# Actuator_Circle.net
KiCad netlist of a schematic drawn in EAGLE
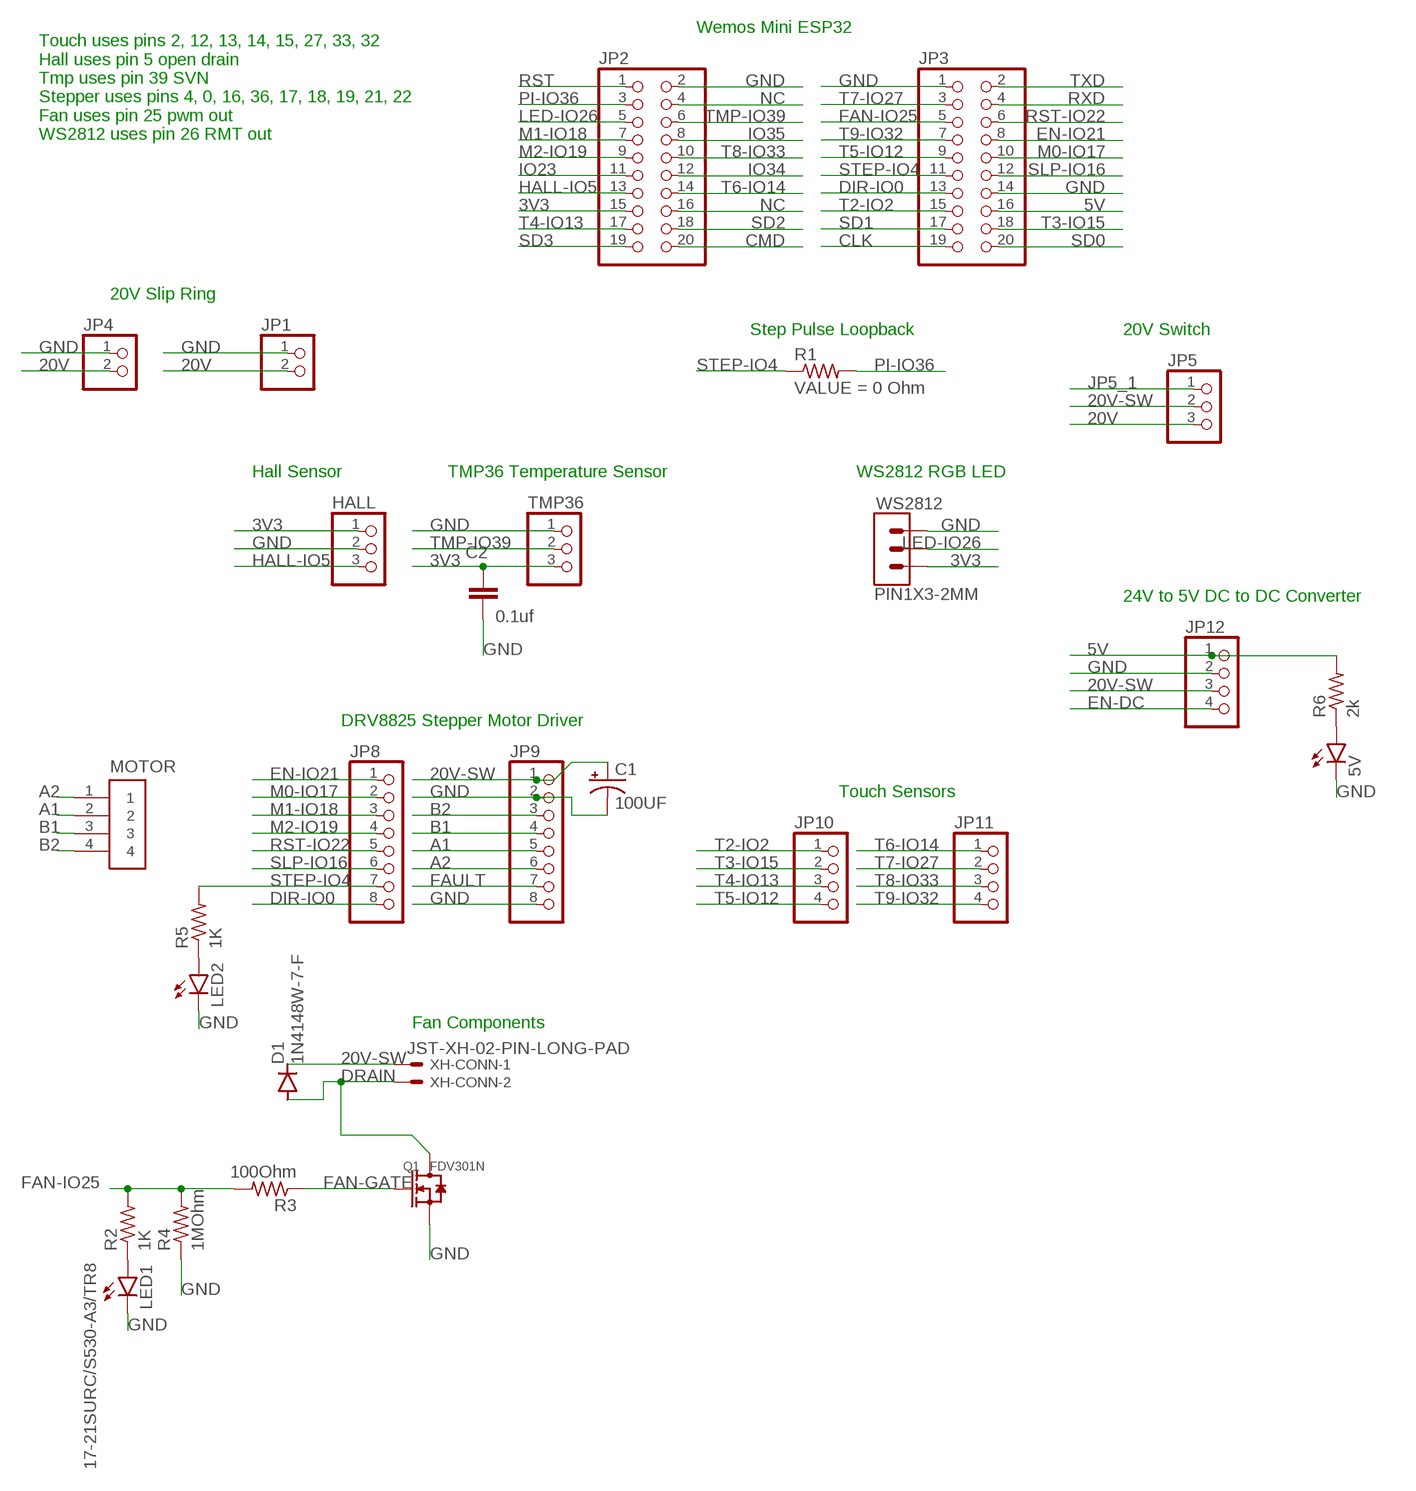
[diagram p0: schematic, sheet 1]

(export (version "E")
  (design (tool "Eeschema 10.0.6"))
  (components
    (comp (ref "5V")
      (value "17-21SURC/S530-A3/TR8")
      (footprint "eagle-import:CHIPLED_0805")
      (libsource (lib "eagle-import") (part "LEDCHIPLED_0805"))
    )
    (comp (ref "C1")
      (value "100UF")
      (footprint "eagle-import:E2,5-6")
      (libsource (lib "eagle-import") (part "CAPACITOR-PE2.5-6"))
    )
    (comp (ref "C2")
      (value "0.1uf")
      (footprint "eagle-import:CAP_0603")
      (fields
        (field (name "DIGIKEY_PART_NUMBER") "LCSC Part #: C86295")
        (field (name "MANUFACTURER") "Samsung Electro-Mechanics")
        (field (name "MPN") " CL10A226MP8NUNE")
        (field (name "CREATED_BY") "ChiliPeppr")
      )
      (libsource (lib "eagle-import") (part "CAP-0603-22UF-10V-MLCC"))
    )
    (comp (ref "D1")
      (value "1N4148W-7-F")
      (footprint "eagle-import:SOD123")
      (libsource (lib "eagle-import") (part "D-SOD123"))
    )
    (comp (ref "HALL")
      (value "PINHD-1X3")
      (footprint "eagle-import:1X03")
      (libsource (lib "eagle-import") (part "pinhead_325_PINHD-1X3"))
    )
    (comp (ref "JP1")
      (value "PINHD-1X2")
      (footprint "eagle-import:1X02")
      (libsource (lib "eagle-import") (part "PINHD-1X2"))
    )
    (comp (ref "JP2")
      (value "PINHD-2X10")
      (footprint "eagle-import:2X10")
      (libsource (lib "eagle-import") (part "PINHD-2X10"))
    )
    (comp (ref "JP3")
      (value "PINHD-2X10")
      (footprint "eagle-import:2X10")
      (libsource (lib "eagle-import") (part "PINHD-2X10"))
    )
    (comp (ref "JP4")
      (value "PINHD-1X2")
      (footprint "eagle-import:1X02")
      (libsource (lib "eagle-import") (part "PINHD-1X2"))
    )
    (comp (ref "JP5")
      (value "PINHD-1X3/90")
      (footprint "eagle-import:1X03_90")
      (libsource (lib "eagle-import") (part "PINHD-1X3/90"))
    )
    (comp (ref "JP8")
      (value "PINHD-1X8")
      (footprint "eagle-import:1X08")
      (libsource (lib "eagle-import") (part "PINHD-1X8"))
    )
    (comp (ref "JP9")
      (value "PINHD-1X8")
      (footprint "eagle-import:1X08")
      (libsource (lib "eagle-import") (part "PINHD-1X8"))
    )
    (comp (ref "JP10")
      (value "PINHD-1X4")
      (footprint "eagle-import:1X04")
      (libsource (lib "eagle-import") (part "PINHD-1X4"))
    )
    (comp (ref "JP11")
      (value "PINHD-1X4")
      (footprint "eagle-import:1X04")
      (libsource (lib "eagle-import") (part "PINHD-1X4"))
    )
    (comp (ref "JP12")
      (value "PINHD-1X4")
      (footprint "eagle-import:1X04")
      (libsource (lib "eagle-import") (part "PINHD-1X4"))
    )
    (comp (ref "LED1")
      (value "17-21SURC/S530-A3/TR8")
      (footprint "eagle-import:CHIPLED_0805")
      (libsource (lib "eagle-import") (part "LEDCHIPLED_0805"))
    )
    (comp (ref "LED2")
      (value "17-21SURC/S530-A3/TR8")
      (footprint "eagle-import:CHIPLED_0805")
      (libsource (lib "eagle-import") (part "LEDCHIPLED_0805"))
    )
    (comp (ref "MOTOR")
      (value "B4B-PH-K-S(LF)(SN)")
      (footprint "eagle-import:JST_B4B-PH-K-S(LF)(SN)")
      (fields (field (name "MF") "JST Sales") (field (name "MP") "B4B-PH-K-S_LF__SN_"))
      (libsource (lib "eagle-import") (part "B4B-PH-K-S(LF)(SN)"))
    )
    (comp (ref "Q1")
      (value "FDV301N")
      (footprint "eagle-import:SOT23")
      (libsource (lib "eagle-import") (part "SMD-MOSFET-N-CH-25V-220MA-FDV301N(SOT-23)"))
    )
    (comp (ref "R1")
      (value "0 Ohm")
      (footprint "eagle-import:RES_0402")
      (fields (field (name "CREATED_BY") "ChiliPeppr"))
      (libsource (lib "eagle-import") (part "robot actuator_11740443_RES-0402"))
    )
    (comp (ref "R2")
      (value "1K")
      (footprint "eagle-import:RES_0402")
      (fields (field (name "CREATED_BY") "ChiliPeppr"))
      (libsource (lib "eagle-import") (part "RES-0402"))
    )
    (comp (ref "R3")
      (value "100Ohm")
      (footprint "eagle-import:RES_0402")
      (fields (field (name "CREATED_BY") "ChiliPeppr"))
      (libsource (lib "eagle-import") (part "RES-0402"))
    )
    (comp (ref "R4")
      (value "1MOhm")
      (footprint "eagle-import:RES_0402")
      (fields (field (name "CREATED_BY") "ChiliPeppr"))
      (libsource (lib "eagle-import") (part "RES-0402"))
    )
    (comp (ref "R5")
      (value "1K")
      (footprint "eagle-import:RES_0402")
      (fields (field (name "CREATED_BY") "ChiliPeppr"))
      (libsource (lib "eagle-import") (part "RES-0402"))
    )
    (comp (ref "R6")
      (value "2k")
      (footprint "eagle-import:RES_0402")
      (fields (field (name "CREATED_BY") "ChiliPeppr"))
      (libsource (lib "eagle-import") (part "RES-0402"))
    )
    (comp (ref "TMP36")
      (value "PINHD-1X3")
      (footprint "eagle-import:1X03")
      (libsource (lib "eagle-import") (part "pinhead_325_PINHD-1X3"))
    )
    (comp (ref "WS2812")
      (value "PIN1X3-2MM")
      (footprint "eagle-import:PIN1X3-2MM")
      (fields
        (field (name "MANUFACTURER") " Würth Elektronik ")
        (field (name "MPN") "62000311121")
        (field (name "CREATED_BY") "PCBLayout.com")
      )
      (libsource (lib "eagle-import") (part "PIN1X3-2MM"))
    )
    (comp (ref "XH-CONN")
      (value "JST-XH-02-PIN-LONG-PAD")
      (footprint "eagle-import:JST-XH-02-PACKAGE-LONG-PAD")
      (libsource (lib "eagle-import") (part "JST-XH-02-PIN-LONG-PAD"))
    )
  )
  (nets
    (net (code "1") (name "/3V3") (class "Default")
      (node (ref "C2") (pin "1") (pinfunction "1_1") (pintype "passive"))
      (node (ref "HALL") (pin "1") (pinfunction "1_1") (pintype "passive"))
      (node (ref "JP2") (pin "15") (pinfunction "15_15") (pintype "passive"))
      (node (ref "TMP36") (pin "3") (pinfunction "3_3") (pintype "passive"))
      (node (ref "WS2812") (pin "3") (pinfunction "3_3") (pintype "passive"))
    )
    (net (code "2") (name "/5V") (class "Default")
      (node (ref "JP12") (pin "1") (pinfunction "1_1") (pintype "passive"))
      (node (ref "JP3") (pin "16") (pinfunction "16_16") (pintype "passive"))
      (node (ref "R6") (pin "2") (pinfunction "2_2") (pintype "passive"))
    )
    (net (code "3") (name "/20V") (class "Default")
      (node (ref "JP1") (pin "2") (pinfunction "2_2") (pintype "passive"))
      (node (ref "JP4") (pin "2") (pinfunction "2_2") (pintype "passive"))
      (node (ref "JP5") (pin "3") (pinfunction "3_3") (pintype "passive"))
    )
    (net (code "4") (name "/20V-SW") (class "Default")
      (node (ref "C1") (pin "+") (pinfunction "+_+") (pintype "passive"))
      (node (ref "D1") (pin "1") (pinfunction "C_1") (pintype "passive"))
      (node (ref "JP12") (pin "3") (pinfunction "3_3") (pintype "passive"))
      (node (ref "JP5") (pin "2") (pinfunction "2_2") (pintype "passive"))
      (node (ref "JP9") (pin "1") (pinfunction "1_1") (pintype "passive"))
      (node (ref "XH-CONN") (pin "1") (pinfunction "S_1") (pintype "passive"))
    )
    (net (code "5") (name "/A1") (class "Default")
      (node (ref "JP9") (pin "5") (pinfunction "5_5") (pintype "passive"))
      (node (ref "MOTOR") (pin "2") (pinfunction "2_2") (pintype "passive"))
    )
    (net (code "6") (name "/A2") (class "Default")
      (node (ref "JP9") (pin "6") (pinfunction "6_6") (pintype "passive"))
      (node (ref "MOTOR") (pin "1") (pinfunction "1_1") (pintype "passive"))
    )
    (net (code "7") (name "/B1") (class "Default")
      (node (ref "JP9") (pin "4") (pinfunction "4_4") (pintype "passive"))
      (node (ref "MOTOR") (pin "3") (pinfunction "3_3") (pintype "passive"))
    )
    (net (code "8") (name "/B2") (class "Default")
      (node (ref "JP9") (pin "3") (pinfunction "3_3") (pintype "passive"))
      (node (ref "MOTOR") (pin "4") (pinfunction "4_4") (pintype "passive"))
    )
    (net (code "9") (name "/CLK") (class "Default")
      (node (ref "JP3") (pin "19") (pinfunction "19_19") (pintype "passive"))
    )
    (net (code "10") (name "/CMD") (class "Default")
      (node (ref "JP2") (pin "20") (pinfunction "20_20") (pintype "passive"))
    )
    (net (code "11") (name "/DIR-IO0") (class "Default")
      (node (ref "JP3") (pin "13") (pinfunction "13_13") (pintype "passive"))
      (node (ref "JP8") (pin "8") (pinfunction "8_8") (pintype "passive"))
    )
    (net (code "12") (name "/DRAIN") (class "Default")
      (node (ref "D1") (pin "2") (pinfunction "A_2") (pintype "passive"))
      (node (ref "Q1") (pin "3") (pinfunction "D_3") (pintype "passive"))
      (node (ref "XH-CONN") (pin "2") (pinfunction "S_2") (pintype "passive"))
    )
    (net (code "13") (name "/EN-DC") (class "Default")
      (node (ref "JP12") (pin "4") (pinfunction "4_4") (pintype "passive"))
    )
    (net (code "14") (name "/EN-IO21") (class "Default")
      (node (ref "JP3") (pin "8") (pinfunction "8_8") (pintype "passive"))
      (node (ref "JP8") (pin "1") (pinfunction "1_1") (pintype "passive"))
    )
    (net (code "15") (name "/FAN-GATE") (class "Default")
      (node (ref "Q1") (pin "1") (pinfunction "G_1") (pintype "passive"))
      (node (ref "R3") (pin "1") (pinfunction "1_1") (pintype "passive"))
    )
    (net (code "16") (name "/FAN-IO25") (class "Default")
      (node (ref "JP3") (pin "5") (pinfunction "5_5") (pintype "passive"))
      (node (ref "R2") (pin "2") (pinfunction "2_2") (pintype "passive"))
      (node (ref "R3") (pin "2") (pinfunction "2_2") (pintype "passive"))
      (node (ref "R4") (pin "2") (pinfunction "2_2") (pintype "passive"))
    )
    (net (code "17") (name "/FAULT") (class "Default")
      (node (ref "JP9") (pin "7") (pinfunction "7_7") (pintype "passive"))
    )
    (net (code "18") (name "/GND") (class "Default")
      (node (ref "5V") (pin "C") (pinfunction "C_C") (pintype "passive"))
      (node (ref "C1") (pin "-") (pinfunction "-_-") (pintype "passive"))
      (node (ref "C2") (pin "2") (pinfunction "2_2") (pintype "passive"))
      (node (ref "HALL") (pin "2") (pinfunction "2_2") (pintype "passive"))
      (node (ref "JP1") (pin "1") (pinfunction "1_1") (pintype "passive"))
      (node (ref "JP12") (pin "2") (pinfunction "2_2") (pintype "passive"))
      (node (ref "JP2") (pin "2") (pinfunction "2_2") (pintype "passive"))
      (node (ref "JP3") (pin "1") (pinfunction "1_1") (pintype "passive"))
      (node (ref "JP3") (pin "14") (pinfunction "14_14") (pintype "passive"))
      (node (ref "JP4") (pin "1") (pinfunction "1_1") (pintype "passive"))
      (node (ref "JP9") (pin "2") (pinfunction "2_2") (pintype "passive"))
      (node (ref "JP9") (pin "8") (pinfunction "8_8") (pintype "passive"))
      (node (ref "LED1") (pin "C") (pinfunction "C_C") (pintype "passive"))
      (node (ref "LED2") (pin "C") (pinfunction "C_C") (pintype "passive"))
      (node (ref "Q1") (pin "2") (pinfunction "S_2") (pintype "passive"))
      (node (ref "R4") (pin "1") (pinfunction "1_1") (pintype "passive"))
      (node (ref "TMP36") (pin "1") (pinfunction "1_1") (pintype "passive"))
      (node (ref "WS2812") (pin "1") (pinfunction "1_1") (pintype "passive"))
    )
    (net (code "19") (name "/HALL-IO5") (class "Default")
      (node (ref "HALL") (pin "3") (pinfunction "3_3") (pintype "passive"))
      (node (ref "JP2") (pin "13") (pinfunction "13_13") (pintype "passive"))
    )
    (net (code "20") (name "/IO23") (class "Default")
      (node (ref "JP2") (pin "11") (pinfunction "11_11") (pintype "passive"))
    )
    (net (code "21") (name "/IO34") (class "Default")
      (node (ref "JP2") (pin "12") (pinfunction "12_12") (pintype "passive"))
    )
    (net (code "22") (name "/IO35") (class "Default")
      (node (ref "JP2") (pin "8") (pinfunction "8_8") (pintype "passive"))
    )
    (net (code "23") (name "/JP5_1") (class "Default")
      (node (ref "JP5") (pin "1") (pinfunction "1_1") (pintype "passive"))
    )
    (net (code "24") (name "/LED-IO26") (class "Default")
      (node (ref "JP2") (pin "5") (pinfunction "5_5") (pintype "passive"))
      (node (ref "WS2812") (pin "2") (pinfunction "2_2") (pintype "passive"))
    )
    (net (code "25") (name "/M0-IO17") (class "Default")
      (node (ref "JP3") (pin "10") (pinfunction "10_10") (pintype "passive"))
      (node (ref "JP8") (pin "2") (pinfunction "2_2") (pintype "passive"))
    )
    (net (code "26") (name "/M1-IO18") (class "Default")
      (node (ref "JP2") (pin "7") (pinfunction "7_7") (pintype "passive"))
      (node (ref "JP8") (pin "3") (pinfunction "3_3") (pintype "passive"))
    )
    (net (code "27") (name "/M2-IO19") (class "Default")
      (node (ref "JP2") (pin "9") (pinfunction "9_9") (pintype "passive"))
      (node (ref "JP8") (pin "4") (pinfunction "4_4") (pintype "passive"))
    )
    (net (code "28") (name "/NC") (class "Default")
      (node (ref "JP2") (pin "16") (pinfunction "16_16") (pintype "passive"))
      (node (ref "JP2") (pin "4") (pinfunction "4_4") (pintype "passive"))
    )
    (net (code "29") (name "/PI-IO36") (class "Default")
      (node (ref "JP2") (pin "3") (pinfunction "3_3") (pintype "passive"))
      (node (ref "R1") (pin "2") (pinfunction "2_2") (pintype "passive"))
    )
    (net (code "30") (name "/RST") (class "Default")
      (node (ref "JP2") (pin "1") (pinfunction "1_1") (pintype "passive"))
    )
    (net (code "31") (name "/RST-IO22") (class "Default")
      (node (ref "JP3") (pin "6") (pinfunction "6_6") (pintype "passive"))
      (node (ref "JP8") (pin "5") (pinfunction "5_5") (pintype "passive"))
    )
    (net (code "32") (name "/RXD") (class "Default")
      (node (ref "JP3") (pin "4") (pinfunction "4_4") (pintype "passive"))
    )
    (net (code "33") (name "/SD0") (class "Default")
      (node (ref "JP3") (pin "20") (pinfunction "20_20") (pintype "passive"))
    )
    (net (code "34") (name "/SD1") (class "Default")
      (node (ref "JP3") (pin "17") (pinfunction "17_17") (pintype "passive"))
    )
    (net (code "35") (name "/SD2") (class "Default")
      (node (ref "JP2") (pin "18") (pinfunction "18_18") (pintype "passive"))
    )
    (net (code "36") (name "/SD3") (class "Default")
      (node (ref "JP2") (pin "19") (pinfunction "19_19") (pintype "passive"))
    )
    (net (code "37") (name "/SLP-IO16") (class "Default")
      (node (ref "JP3") (pin "12") (pinfunction "12_12") (pintype "passive"))
      (node (ref "JP8") (pin "6") (pinfunction "6_6") (pintype "passive"))
    )
    (net (code "38") (name "/STEP-IO4") (class "Default")
      (node (ref "JP3") (pin "11") (pinfunction "11_11") (pintype "passive"))
      (node (ref "JP8") (pin "7") (pinfunction "7_7") (pintype "passive"))
      (node (ref "R1") (pin "1") (pinfunction "1_1") (pintype "passive"))
      (node (ref "R5") (pin "2") (pinfunction "2_2") (pintype "passive"))
    )
    (net (code "39") (name "/T2-IO2") (class "Default")
      (node (ref "JP10") (pin "1") (pinfunction "1_1") (pintype "passive"))
      (node (ref "JP3") (pin "15") (pinfunction "15_15") (pintype "passive"))
    )
    (net (code "40") (name "/T3-IO15") (class "Default")
      (node (ref "JP10") (pin "2") (pinfunction "2_2") (pintype "passive"))
      (node (ref "JP3") (pin "18") (pinfunction "18_18") (pintype "passive"))
    )
    (net (code "41") (name "/T4-IO13") (class "Default")
      (node (ref "JP10") (pin "3") (pinfunction "3_3") (pintype "passive"))
      (node (ref "JP2") (pin "17") (pinfunction "17_17") (pintype "passive"))
    )
    (net (code "42") (name "/T5-IO12") (class "Default")
      (node (ref "JP10") (pin "4") (pinfunction "4_4") (pintype "passive"))
      (node (ref "JP3") (pin "9") (pinfunction "9_9") (pintype "passive"))
    )
    (net (code "43") (name "/T6-IO14") (class "Default")
      (node (ref "JP11") (pin "1") (pinfunction "1_1") (pintype "passive"))
      (node (ref "JP2") (pin "14") (pinfunction "14_14") (pintype "passive"))
    )
    (net (code "44") (name "/T7-IO27") (class "Default")
      (node (ref "JP11") (pin "2") (pinfunction "2_2") (pintype "passive"))
      (node (ref "JP3") (pin "3") (pinfunction "3_3") (pintype "passive"))
    )
    (net (code "45") (name "/T8-IO33") (class "Default")
      (node (ref "JP11") (pin "3") (pinfunction "3_3") (pintype "passive"))
      (node (ref "JP2") (pin "10") (pinfunction "10_10") (pintype "passive"))
    )
    (net (code "46") (name "/T9-IO32") (class "Default")
      (node (ref "JP11") (pin "4") (pinfunction "4_4") (pintype "passive"))
      (node (ref "JP3") (pin "7") (pinfunction "7_7") (pintype "passive"))
    )
    (net (code "47") (name "/TMP-IO39") (class "Default")
      (node (ref "JP2") (pin "6") (pinfunction "6_6") (pintype "passive"))
      (node (ref "TMP36") (pin "2") (pinfunction "2_2") (pintype "passive"))
    )
    (net (code "48") (name "/TXD") (class "Default")
      (node (ref "JP3") (pin "2") (pinfunction "2_2") (pintype "passive"))
    )
    (net (code "49") (name "Net-(5V-PadA)") (class "Default")
      (node (ref "5V") (pin "A") (pinfunction "A_A") (pintype "passive"))
      (node (ref "R6") (pin "1") (pinfunction "1_1") (pintype "passive"))
    )
    (net (code "50") (name "Net-(LED1-PadA)") (class "Default")
      (node (ref "LED1") (pin "A") (pinfunction "A_A") (pintype "passive"))
      (node (ref "R2") (pin "1") (pinfunction "1_1") (pintype "passive"))
    )
    (net (code "51") (name "Net-(LED2-PadA)") (class "Default")
      (node (ref "LED2") (pin "A") (pinfunction "A_A") (pintype "passive"))
      (node (ref "R5") (pin "1") (pinfunction "1_1") (pintype "passive"))
    )
  )
)
